# PowerBuck.net
KiCad netlist of a schematic drawn in Altium Designer
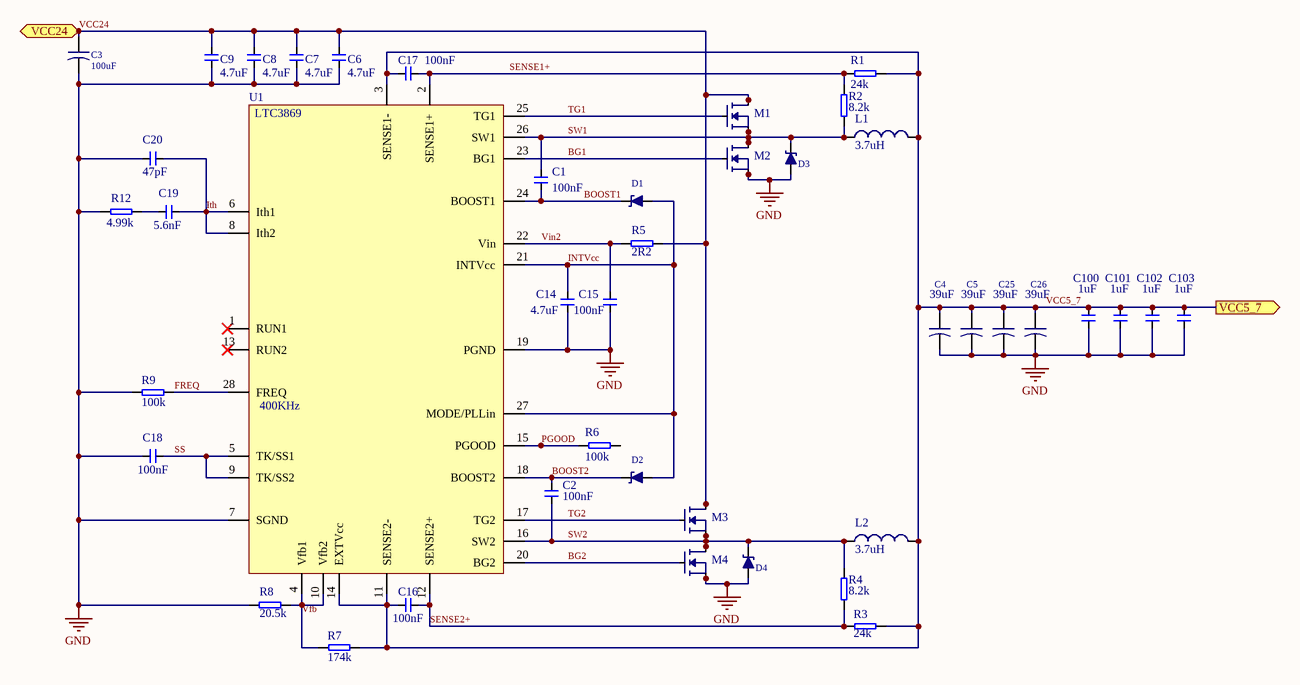
[diagram p0: PowerBuck.SchDoc]

(export (version "E")
  (design (tool "Eeschema 10.0.6"))
  (components
    (comp (ref "C1")
      (value "100nF")
      (footprint "Controller:CAP 0603/1608")
      (description "Capacitor")
      (libsource (lib "Controller") (part "CAP"))
    )
    (comp (ref "C2")
      (value "100nF")
      (footprint "Controller:CAP 0603/1608")
      (description "Capacitor")
      (libsource (lib "Controller") (part "CAP"))
    )
    (comp (ref "C3")
      (value "100uF")
      (footprint "CAPAE115102X102N")
      (libsource (lib "Controller") (part "E CAP"))
    )
    (comp (ref "C4") (value "39uF") (footprint "CAPAE6053X59M") (libsource (lib "Controller") (part "E CAP")))
    (comp (ref "C5") (value "39uF") (footprint "CAPAE6053X59M") (libsource (lib "Controller") (part "E CAP")))
    (comp (ref "C6")
      (value "4.7uF")
      (footprint "Controller:CAP_1206")
      (description "Capacitor")
      (libsource (lib "Controller") (part "CAP"))
    )
    (comp (ref "C7")
      (value "4.7uF")
      (footprint "Controller:CAP_1206")
      (description "Capacitor")
      (libsource (lib "Controller") (part "CAP"))
    )
    (comp (ref "C8")
      (value "4.7uF")
      (footprint "Controller:CAP_1206")
      (description "Capacitor")
      (libsource (lib "Controller") (part "CAP"))
    )
    (comp (ref "C9")
      (value "4.7uF")
      (footprint "Controller:CAP_1206")
      (description "Capacitor")
      (libsource (lib "Controller") (part "CAP"))
    )
    (comp (ref "C14")
      (value "4.7uF")
      (footprint "Controller:CAP_1206")
      (description "Capacitor")
      (libsource (lib "Controller") (part "CAP"))
    )
    (comp (ref "C15")
      (value "100nF")
      (footprint "Controller:CAP 0603/1608")
      (description "Capacitor")
      (libsource (lib "Controller") (part "CAP"))
    )
    (comp (ref "C16")
      (value "100nF")
      (footprint "Controller:CAP 0603/1608")
      (description "Capacitor")
      (libsource (lib "Controller") (part "CAP"))
    )
    (comp (ref "C17")
      (value "100nF")
      (footprint "Controller:CAP 0603/1608")
      (description "Capacitor")
      (libsource (lib "Controller") (part "CAP"))
    )
    (comp (ref "C18")
      (value "100nF")
      (footprint "Controller:CAP 0603/1608")
      (description "Capacitor")
      (libsource (lib "Controller") (part "CAP"))
    )
    (comp (ref "C19")
      (value "5.6nF")
      (footprint "Controller:CAP 0603/1608")
      (description "Capacitor")
      (libsource (lib "Controller") (part "CAP"))
    )
    (comp (ref "C20")
      (value "47pF")
      (footprint "Controller:CAP 0603/1608")
      (description "Capacitor")
      (libsource (lib "Controller") (part "CAP"))
    )
    (comp (ref "C25")
      (value "39uF")
      (footprint "CAPAE6053X59M")
      (libsource (lib "Controller") (part "E CAP"))
    )
    (comp (ref "C26")
      (value "39uF")
      (footprint "CAPAE6053X59M")
      (libsource (lib "Controller") (part "E CAP"))
    )
    (comp (ref "C100")
      (value "1uF")
      (footprint "Controller:CAP1206")
      (description "Capacitor")
      (libsource (lib "Controller") (part "CAP"))
    )
    (comp (ref "C101")
      (value "1uF")
      (footprint "Controller:CAP1206")
      (description "Capacitor")
      (libsource (lib "Controller") (part "CAP"))
    )
    (comp (ref "C102")
      (value "1uF")
      (footprint "Controller:CAP1206")
      (description "Capacitor")
      (libsource (lib "Controller") (part "CAP"))
    )
    (comp (ref "C103")
      (value "1uF")
      (footprint "Controller:CAP1206")
      (description "Capacitor")
      (libsource (lib "Controller") (part "CAP"))
    )
    (comp (ref "D1")
      (value "SDM10K45")
      (footprint "DIOM1713X11N")
      (libsource (lib "Controller") (part "D Schottky"))
    )
    (comp (ref "D2")
      (value "SDM10K45")
      (footprint "DIOM1713X11N")
      (libsource (lib "Controller") (part "D Schottky"))
    )
    (comp (ref "D3")
      (value "SDM10K45")
      (footprint "DIOM2618X11N")
      (libsource (lib "Controller") (part "D Schottky"))
    )
    (comp (ref "D4")
      (value "SDM10K45")
      (footprint "DIOM2618X11N")
      (libsource (lib "Controller") (part "D Schottky"))
    )
    (comp (ref "L1")
      (value "3.7uH")
      (footprint "Controller:INDP130128X62N")
      (description "Inductor")
      (fields (field (name "PUBLISHER") "Altium Limited"))
      (libsource (lib "Controller") (part "Inductor"))
    )
    (comp (ref "L2")
      (value "3.7uH")
      (footprint "Controller:INDP130128X62N")
      (description "Inductor")
      (fields (field (name "PUBLISHER") "Altium Limited"))
      (libsource (lib "Controller") (part "Inductor"))
    )
    (comp (ref "M1")
      (value "MOSFET-N")
      (footprint "controller:INF-PG-TDSON-8-1_V")
      (libsource (lib "Controller") (part "MOSFET-N"))
    )
    (comp (ref "M2")
      (value "MOSFET-N")
      (footprint "controller:INF-PG-TDSON-8-1_V")
      (libsource (lib "Controller") (part "MOSFET-N"))
    )
    (comp (ref "M3")
      (value "MOSFET-N")
      (footprint "controller:INF-PG-TDSON-8-1_V")
      (libsource (lib "Controller") (part "MOSFET-N"))
    )
    (comp (ref "M4")
      (value "MOSFET-N")
      (footprint "Controller:INF-PG-TDSON-8-1_V")
      (libsource (lib "Controller") (part "MOSFET-N"))
    )
    (comp (ref "R1")
      (value "24k")
      (footprint "Controller:RES 0603/1608")
      (description "Resistor")
      (libsource (lib "Controller") (part "RES"))
    )
    (comp (ref "R2")
      (value "8.2k")
      (footprint "Controller:RES 0603/1608")
      (description "Resistor")
      (libsource (lib "Controller") (part "RES"))
    )
    (comp (ref "R3")
      (value "24k")
      (footprint "Controller:RES 0603/1608")
      (description "Resistor")
      (libsource (lib "Controller") (part "RES"))
    )
    (comp (ref "R4")
      (value "8.2k")
      (footprint "Controller:RES 0603/1608")
      (description "Resistor")
      (libsource (lib "Controller") (part "RES"))
    )
    (comp (ref "R5")
      (value "2R2")
      (footprint "Controller:RES 0603/1608")
      (description "Resistor")
      (libsource (lib "Controller") (part "RES"))
    )
    (comp (ref "R6")
      (value "100k")
      (footprint "Controller:RES 0603/1608")
      (description "Resistor")
      (libsource (lib "Controller") (part "RES"))
    )
    (comp (ref "R7")
      (value "174k")
      (footprint "Controller:RES 0603/1608")
      (description "Resistor")
      (libsource (lib "Controller") (part "RES"))
    )
    (comp (ref "R8")
      (value "20.5k")
      (footprint "Controller:RES 0603/1608")
      (description "Resistor")
      (libsource (lib "altium-import") (part "root_0_RES_"))
    )
    (comp (ref "R9")
      (value "100k")
      (footprint "Controller:RES 0603/1608")
      (description "Resistor")
      (libsource (lib "Controller") (part "RES"))
    )
    (comp (ref "R12")
      (value "4.99k")
      (footprint "Controller:RES 0603/1608")
      (description "Resistor")
      (libsource (lib "Controller") (part "RES"))
    )
    (comp (ref "U1")
      (value "LTC3869")
      (footprint "SOP64P600X175-28N")
      (libsource (lib "Controller") (part "LTC3869"))
    )
  )
  (nets
    (net (code "1") (name "/BG1") (class "Default")
      (node (ref "M2") (pin "4") (pinfunction "G_4") (pintype "passive"))
      (node (ref "U1") (pin "23") (pinfunction "BG1_23") (pintype "passive"))
    )
    (net (code "2") (name "/BG2") (class "Default")
      (node (ref "M4") (pin "4") (pinfunction "G_4") (pintype "passive"))
      (node (ref "U1") (pin "20") (pinfunction "BG2_20") (pintype "passive"))
    )
    (net (code "3") (name "/BOOST1") (class "Default")
      (node (ref "C1") (pin "2") (pinfunction "2_2") (pintype "passive"))
      (node (ref "D1") (pin "1") (pintype "power_in"))
      (node (ref "U1") (pin "24") (pinfunction "BOOST1_24") (pintype "passive"))
    )
    (net (code "4") (name "/BOOST2") (class "Default")
      (node (ref "C2") (pin "1") (pinfunction "1_1") (pintype "passive"))
      (node (ref "D2") (pin "1") (pintype "power_in"))
      (node (ref "U1") (pin "18") (pinfunction "BOOST2_18") (pintype "passive"))
    )
    (net (code "5") (name "/FREQ") (class "Default")
      (node (ref "R9") (pin "1") (pinfunction "1_1") (pintype "passive"))
      (node (ref "U1") (pin "28") (pinfunction "FREQ_28") (pintype "passive"))
    )
    (net (code "6") (name "/INTVcc") (class "Default")
      (node (ref "C14") (pin "1") (pinfunction "1_1") (pintype "passive"))
      (node (ref "D1") (pin "2") (pintype "power_in"))
      (node (ref "D2") (pin "2") (pintype "power_in"))
      (node (ref "U1") (pin "21") (pinfunction "INTVcc_21") (pintype "passive"))
      (node (ref "U1") (pin "27") (pinfunction "MODE/PLLin_27") (pintype "passive"))
    )
    (net (code "7") (name "/Ith") (class "Default")
      (node (ref "C19") (pin "1") (pinfunction "1_1") (pintype "passive"))
      (node (ref "C20") (pin "1") (pinfunction "1_1") (pintype "passive"))
      (node (ref "U1") (pin "6") (pinfunction "Ith1_6") (pintype "passive"))
      (node (ref "U1") (pin "8") (pinfunction "Ith2_8") (pintype "passive"))
    )
    (net (code "8") (name "/PGOOD") (class "Default")
      (node (ref "R6") (pin "2") (pinfunction "2_2") (pintype "passive"))
      (node (ref "U1") (pin "15") (pinfunction "PGOOD_15") (pintype "passive"))
    )
    (net (code "9") (name "/SENSE1+") (class "Default")
      (node (ref "C17") (pin "2") (pinfunction "2_2") (pintype "passive"))
      (node (ref "R1") (pin "2") (pinfunction "2_2") (pintype "passive"))
      (node (ref "R2") (pin "2") (pinfunction "2_2") (pintype "passive"))
      (node (ref "U1") (pin "2") (pinfunction "SENSE1+_2") (pintype "passive"))
    )
    (net (code "10") (name "/SENSE2+") (class "Default")
      (node (ref "C16") (pin "2") (pinfunction "2_2") (pintype "passive"))
      (node (ref "R3") (pin "1") (pinfunction "1_1") (pintype "passive"))
      (node (ref "R4") (pin "2") (pinfunction "2_2") (pintype "passive"))
      (node (ref "U1") (pin "12") (pinfunction "SENSE2+_12") (pintype "passive"))
    )
    (net (code "11") (name "/SS") (class "Default")
      (node (ref "C18") (pin "1") (pinfunction "1_1") (pintype "passive"))
      (node (ref "U1") (pin "5") (pinfunction "TK/SS1_5") (pintype "passive"))
      (node (ref "U1") (pin "9") (pinfunction "TK/SS2_9") (pintype "passive"))
    )
    (net (code "12") (name "/SW1") (class "Default")
      (node (ref "C1") (pin "1") (pinfunction "1_1") (pintype "passive"))
      (node (ref "D3") (pin "1") (pintype "power_in"))
      (node (ref "L1") (pin "1") (pinfunction "1_1") (pintype "passive"))
      (node (ref "M1") (pin "1") (pinfunction "S_1") (pintype "passive"))
      (node (ref "M1") (pin "2") (pinfunction "S_2") (pintype "passive"))
      (node (ref "M1") (pin "3") (pinfunction "S_3") (pintype "passive"))
      (node (ref "M2") (pin "5") (pinfunction "D_5") (pintype "passive"))
      (node (ref "M2") (pin "6") (pinfunction "D_6") (pintype "passive"))
      (node (ref "M2") (pin "7") (pinfunction "D_7") (pintype "passive"))
      (node (ref "M2") (pin "8") (pinfunction "8_8") (pintype "passive"))
      (node (ref "R2") (pin "1") (pinfunction "1_1") (pintype "passive"))
      (node (ref "U1") (pin "26") (pinfunction "SW1_26") (pintype "passive"))
    )
    (net (code "13") (name "/SW2") (class "Default")
      (node (ref "C2") (pin "2") (pinfunction "2_2") (pintype "passive"))
      (node (ref "D4") (pin "1") (pintype "power_in"))
      (node (ref "L2") (pin "1") (pinfunction "1_1") (pintype "passive"))
      (node (ref "M3") (pin "1") (pinfunction "S_1") (pintype "passive"))
      (node (ref "M3") (pin "2") (pinfunction "S_2") (pintype "passive"))
      (node (ref "M3") (pin "3") (pinfunction "S_3") (pintype "passive"))
      (node (ref "M4") (pin "5") (pinfunction "D_5") (pintype "passive"))
      (node (ref "M4") (pin "6") (pinfunction "D_6") (pintype "passive"))
      (node (ref "M4") (pin "7") (pinfunction "D_7") (pintype "passive"))
      (node (ref "M4") (pin "8") (pinfunction "8_8") (pintype "passive"))
      (node (ref "R4") (pin "1") (pinfunction "1_1") (pintype "passive"))
      (node (ref "U1") (pin "16") (pinfunction "SW2_16") (pintype "passive"))
    )
    (net (code "14") (name "/TG1") (class "Default")
      (node (ref "M1") (pin "4") (pinfunction "G_4") (pintype "passive"))
      (node (ref "U1") (pin "25") (pinfunction "TG1_25") (pintype "passive"))
    )
    (net (code "15") (name "/TG2") (class "Default")
      (node (ref "M3") (pin "4") (pinfunction "G_4") (pintype "passive"))
      (node (ref "U1") (pin "17") (pinfunction "TG2_17") (pintype "passive"))
    )
    (net (code "16") (name "/VCC5_7") (class "Default")
      (node (ref "C100") (pin "2") (pinfunction "2_2") (pintype "passive"))
      (node (ref "C101") (pin "1") (pinfunction "1_1") (pintype "passive"))
      (node (ref "C102") (pin "1") (pinfunction "1_1") (pintype "passive"))
      (node (ref "C103") (pin "1") (pinfunction "1_1") (pintype "passive"))
      (node (ref "C16") (pin "1") (pinfunction "1_1") (pintype "passive"))
      (node (ref "C17") (pin "1") (pinfunction "1_1") (pintype "passive"))
      (node (ref "C25") (pin "1") (pinfunction "0_1") (pintype "passive"))
      (node (ref "C26") (pin "1") (pinfunction "0_1") (pintype "passive"))
      (node (ref "C4") (pin "1") (pinfunction "0_1") (pintype "passive"))
      (node (ref "C5") (pin "1") (pinfunction "0_1") (pintype "passive"))
      (node (ref "L1") (pin "2") (pinfunction "2_2") (pintype "passive"))
      (node (ref "L2") (pin "2") (pinfunction "2_2") (pintype "passive"))
      (node (ref "R1") (pin "1") (pinfunction "1_1") (pintype "passive"))
      (node (ref "R3") (pin "2") (pinfunction "2_2") (pintype "passive"))
      (node (ref "R7") (pin "2") (pinfunction "2_2") (pintype "passive"))
      (node (ref "U1") (pin "11") (pinfunction "SENSE2-_11") (pintype "passive"))
      (node (ref "U1") (pin "14") (pinfunction "EXTVcc_14") (pintype "passive"))
      (node (ref "U1") (pin "3") (pinfunction "SENSE1-_3") (pintype "passive"))
    )
    (net (code "17") (name "/VCC24") (class "Default")
      (node (ref "C3") (pin "1") (pinfunction "0_1") (pintype "passive"))
      (node (ref "C6") (pin "1") (pinfunction "1_1") (pintype "passive"))
      (node (ref "C7") (pin "1") (pinfunction "1_1") (pintype "passive"))
      (node (ref "C8") (pin "1") (pinfunction "1_1") (pintype "passive"))
      (node (ref "C9") (pin "1") (pinfunction "1_1") (pintype "passive"))
      (node (ref "M1") (pin "5") (pinfunction "D_5") (pintype "passive"))
      (node (ref "M1") (pin "6") (pinfunction "D_6") (pintype "passive"))
      (node (ref "M1") (pin "7") (pinfunction "D_7") (pintype "passive"))
      (node (ref "M1") (pin "8") (pinfunction "8_8") (pintype "passive"))
      (node (ref "M3") (pin "5") (pinfunction "D_5") (pintype "passive"))
      (node (ref "M3") (pin "6") (pinfunction "D_6") (pintype "passive"))
      (node (ref "M3") (pin "7") (pinfunction "D_7") (pintype "passive"))
      (node (ref "M3") (pin "8") (pinfunction "8_8") (pintype "passive"))
      (node (ref "R5") (pin "1") (pinfunction "1_1") (pintype "passive"))
    )
    (net (code "18") (name "/Vfb") (class "Default")
      (node (ref "R7") (pin "1") (pinfunction "1_1") (pintype "passive"))
      (node (ref "R8") (pin "1") (pinfunction "1_1") (pintype "passive"))
      (node (ref "U1") (pin "10") (pinfunction "Vfb2_10") (pintype "passive"))
      (node (ref "U1") (pin "4") (pinfunction "Vfb1_4") (pintype "passive"))
    )
    (net (code "19") (name "/Vin2") (class "Default")
      (node (ref "C15") (pin "1") (pinfunction "1_1") (pintype "passive"))
      (node (ref "R5") (pin "2") (pinfunction "2_2") (pintype "passive"))
      (node (ref "U1") (pin "22") (pinfunction "Vin_22") (pintype "passive"))
    )
    (net (code "20") (name "GND") (class "Default")
      (node (ref "C100") (pin "1") (pinfunction "1_1") (pintype "passive"))
      (node (ref "C101") (pin "2") (pinfunction "2_2") (pintype "passive"))
      (node (ref "C102") (pin "2") (pinfunction "2_2") (pintype "passive"))
      (node (ref "C103") (pin "2") (pinfunction "2_2") (pintype "passive"))
      (node (ref "C14") (pin "2") (pinfunction "2_2") (pintype "passive"))
      (node (ref "C15") (pin "2") (pinfunction "2_2") (pintype "passive"))
      (node (ref "C18") (pin "2") (pinfunction "2_2") (pintype "passive"))
      (node (ref "C20") (pin "2") (pinfunction "2_2") (pintype "passive"))
      (node (ref "C25") (pin "2") (pinfunction "1_2") (pintype "passive"))
      (node (ref "C26") (pin "2") (pinfunction "1_2") (pintype "passive"))
      (node (ref "C3") (pin "2") (pinfunction "1_2") (pintype "passive"))
      (node (ref "C4") (pin "2") (pinfunction "1_2") (pintype "passive"))
      (node (ref "C5") (pin "2") (pinfunction "1_2") (pintype "passive"))
      (node (ref "C6") (pin "2") (pinfunction "2_2") (pintype "passive"))
      (node (ref "C7") (pin "2") (pinfunction "2_2") (pintype "passive"))
      (node (ref "C8") (pin "2") (pinfunction "2_2") (pintype "passive"))
      (node (ref "C9") (pin "2") (pinfunction "2_2") (pintype "passive"))
      (node (ref "D3") (pin "2") (pintype "power_in"))
      (node (ref "D4") (pin "2") (pintype "power_in"))
      (node (ref "M2") (pin "1") (pinfunction "S_1") (pintype "passive"))
      (node (ref "M2") (pin "2") (pinfunction "S_2") (pintype "passive"))
      (node (ref "M2") (pin "3") (pinfunction "S_3") (pintype "passive"))
      (node (ref "M4") (pin "1") (pinfunction "S_1") (pintype "passive"))
      (node (ref "M4") (pin "2") (pinfunction "S_2") (pintype "passive"))
      (node (ref "M4") (pin "3") (pinfunction "S_3") (pintype "passive"))
      (node (ref "R12") (pin "2") (pinfunction "2_2") (pintype "passive"))
      (node (ref "R8") (pin "2") (pinfunction "2_2") (pintype "passive"))
      (node (ref "R9") (pin "2") (pinfunction "2_2") (pintype "passive"))
      (node (ref "U1") (pin "19") (pinfunction "PGND_19") (pintype "passive"))
      (node (ref "U1") (pin "7") (pinfunction "SGND_7") (pintype "passive"))
    )
    (net (code "21") (name "Net-(C19-Pad2)") (class "Default")
      (node (ref "C19") (pin "2") (pinfunction "2_2") (pintype "passive"))
      (node (ref "R12") (pin "1") (pinfunction "1_1") (pintype "passive"))
    )
    (net (code "22") (name "unconnected-(R6-Pad1)") (class "Default")
      (node (ref "R6") (pin "1") (pinfunction "1_1") (pintype "passive"))
    )
    (net (code "23") (name "unconnected-(U1-RUN1-Pad1)") (class "Default")
      (node (ref "U1") (pin "1") (pinfunction "RUN1_1") (pintype "passive+no_connect"))
    )
    (net (code "24") (name "unconnected-(U1-RUN2-Pad13)") (class "Default")
      (node (ref "U1") (pin "13") (pinfunction "RUN2_13") (pintype "passive+no_connect"))
    )
  )
)
